# uC.net
KiCad netlist of a schematic drawn in Altium Designer
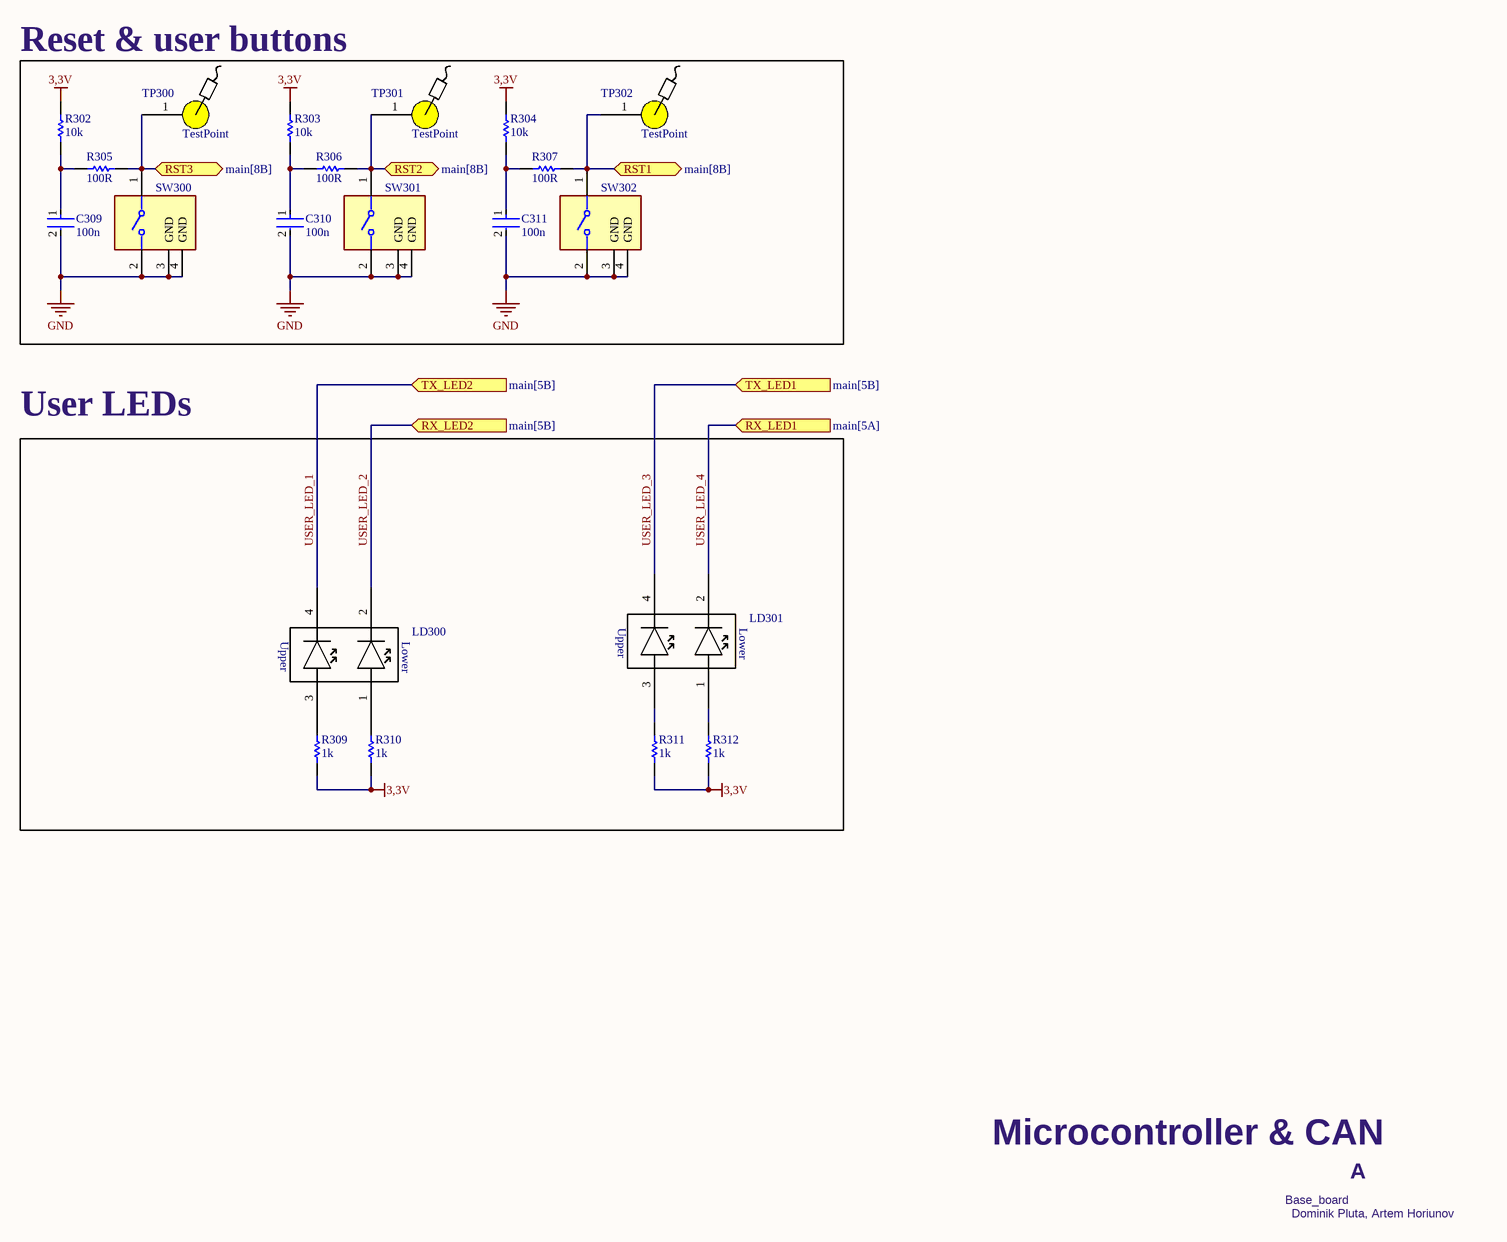
[diagram p0: uC.SchDoc]

(export (version "E")
  (design (tool "Eeschema 10.0.6"))
  (components
    (comp (ref "C309")
      (value "100n")
      (footprint "FP-C0603C-CF-MFG")
      (description "CAP CER 0.1UF 50V X7R 0603")
      (fields (field (name "TOLERANCE") "0.1") (field (name "MANUFACTURER") "KEMET"))
      (libsource (lib "Altium Content Vault") (part "b4654b650e69147ec39a6b967a45e02"))
    )
    (comp (ref "C310")
      (value "100n")
      (footprint "FP-C0603C-CF-MFG")
      (description "CAP CER 0.1UF 50V X7R 0603")
      (fields (field (name "TOLERANCE") "0.1") (field (name "MANUFACTURER") "KEMET"))
      (libsource (lib "Altium Content Vault") (part "b4654b650e69147ec39a6b967a45e02"))
    )
    (comp (ref "C311")
      (value "100n")
      (footprint "FP-C0603C-CF-MFG")
      (description "CAP CER 0.1UF 50V X7R 0603")
      (fields (field (name "TOLERANCE") "0.1") (field (name "MANUFACTURER") "KEMET"))
      (libsource (lib "Altium Content Vault") (part "b4654b650e69147ec39a6b967a45e02"))
    )
    (comp (ref "LD300")
      (value "~")
      (footprint "LedHolder:LED_HOLDER")
      (libsource (lib "LedHolder") (part "DoubleStack_Side_Led_3mm"))
    )
    (comp (ref "LD301")
      (value "~")
      (footprint "LedHolder:LED_HOLDER")
      (libsource (lib "LedHolder") (part "DoubleStack_Side_Led_3mm"))
    )
    (comp (ref "R302")
      (value "10k")
      (footprint "RESC0603(1608)_N")
      (description "0.1W 5% 0603 (1608 Metric)  SMD")
      (fields (field (name "TOLERANCE") "5 %") (field (name "POWER") "0.1 W"))
      (libsource (lib "Altium Content Vault") (part "RES"))
    )
    (comp (ref "R303")
      (value "10k")
      (footprint "RESC0603(1608)_N")
      (description "0.1W 5% 0603 (1608 Metric)  SMD")
      (fields (field (name "TOLERANCE") "5 %") (field (name "POWER") "0.1 W"))
      (libsource (lib "Altium Content Vault") (part "RES"))
    )
    (comp (ref "R304")
      (value "10k")
      (footprint "RESC0603(1608)_N")
      (description "0.1W 5% 0603 (1608 Metric)  SMD")
      (fields (field (name "TOLERANCE") "5 %") (field (name "POWER") "0.1 W"))
      (libsource (lib "Altium Content Vault") (part "RES"))
    )
    (comp (ref "R305")
      (value "100R")
      (footprint "RESC0603(1608)_N")
      (description "0.1W 5% 0603 (1608 Metric)  SMD")
      (fields (field (name "TOLERANCE") "5 %") (field (name "POWER") "0.1 W"))
      (libsource (lib "Altium Content Vault") (part "RES"))
    )
    (comp (ref "R306")
      (value "100R")
      (footprint "RESC0603(1608)_N")
      (description "0.1W 5% 0603 (1608 Metric)  SMD")
      (fields (field (name "TOLERANCE") "5 %") (field (name "POWER") "0.1 W"))
      (libsource (lib "Altium Content Vault") (part "RES"))
    )
    (comp (ref "R307")
      (value "100R")
      (footprint "RESC0603(1608)_N")
      (description "0.1W 5% 0603 (1608 Metric)  SMD")
      (fields (field (name "TOLERANCE") "5 %") (field (name "POWER") "0.1 W"))
      (libsource (lib "Altium Content Vault") (part "RES"))
    )
    (comp (ref "R309")
      (value "1k")
      (footprint "RESC0603(1608)_N")
      (description "0.1W 1% 0603 (1608 Metric)  SMD")
      (fields (field (name "TOLERANCE") "5 %") (field (name "POWER") "0.1 W"))
      (libsource (lib "Altium Content Vault") (part "RES"))
    )
    (comp (ref "R310")
      (value "1k")
      (footprint "RESC0603(1608)_N")
      (description "0.1W 1% 0603 (1608 Metric)  SMD")
      (fields (field (name "TOLERANCE") "5 %") (field (name "POWER") "0.1 W"))
      (libsource (lib "Altium Content Vault") (part "RES"))
    )
    (comp (ref "R311")
      (value "1k")
      (footprint "RESC0603(1608)_N")
      (description "0.1W 1% 0603 (1608 Metric)  SMD")
      (fields (field (name "TOLERANCE") "5 %") (field (name "POWER") "0.1 W"))
      (libsource (lib "Altium Content Vault") (part "RES"))
    )
    (comp (ref "R312")
      (value "1k")
      (footprint "RESC0603(1608)_N")
      (description "0.1W 1% 0603 (1608 Metric)  SMD")
      (fields (field (name "TOLERANCE") "5 %") (field (name "POWER") "0.1 W"))
      (libsource (lib "Altium Content Vault") (part "RES"))
    )
    (comp (ref "SW300")
      (value "B3F-3122")
      (footprint "FP-B3F-3122-MFG")
      (description "SWITCH TACTILE SPST-NO 0.05A 24V")
      (libsource (lib "Altium Content Vault") (part "05c531d4b500f7e9514fa3f65f375ae"))
    )
    (comp (ref "SW301")
      (value "B3F-3122")
      (footprint "FP-B3F-3122-MFG")
      (description "SWITCH TACTILE SPST-NO 0.05A 24V")
      (libsource (lib "Altium Content Vault") (part "05c531d4b500f7e9514fa3f65f375ae"))
    )
    (comp (ref "SW302")
      (value "B3F-3122")
      (footprint "FP-B3F-3122-MFG")
      (description "SWITCH TACTILE SPST-NO 0.05A 24V")
      (libsource (lib "Altium Content Vault") (part "05c531d4b500f7e9514fa3f65f375ae"))
    )
    (comp (ref "TP300")
      (value "TestPoint")
      (footprint "TestPoint")
      (libsource (lib "TestPoint") (part "TestPoint"))
    )
    (comp (ref "TP301")
      (value "TestPoint")
      (footprint "TestPoint")
      (libsource (lib "TestPoint") (part "TestPoint"))
    )
    (comp (ref "TP302")
      (value "TestPoint")
      (footprint "TestPoint")
      (libsource (lib "TestPoint") (part "TestPoint"))
    )
  )
  (nets
    (net (code "1") (name "/RST1") (class "Default")
      (node (ref "R307") (pin "1") (pinfunction "1_1") (pintype "passive"))
      (node (ref "SW302") (pin "1") (pinfunction "1_1") (pintype "passive"))
      (node (ref "TP302") (pin "1") (pintype "passive"))
    )
    (net (code "2") (name "/RST2") (class "Default")
      (node (ref "R306") (pin "1") (pinfunction "1_1") (pintype "passive"))
      (node (ref "SW301") (pin "1") (pinfunction "1_1") (pintype "passive"))
      (node (ref "TP301") (pin "1") (pintype "passive"))
    )
    (net (code "3") (name "/RST3") (class "Default")
      (node (ref "R305") (pin "1") (pinfunction "1_1") (pintype "passive"))
      (node (ref "SW300") (pin "1") (pinfunction "1_1") (pintype "passive"))
      (node (ref "TP300") (pin "1") (pintype "passive"))
    )
    (net (code "4") (name "/USER_LED_1") (class "Default") (node (ref "LD300") (pin "4") (pintype "passive")))
    (net (code "5") (name "/USER_LED_2") (class "Default") (node (ref "LD300") (pin "2") (pintype "passive")))
    (net (code "6") (name "/USER_LED_3") (class "Default") (node (ref "LD301") (pin "4") (pintype "passive")))
    (net (code "7") (name "/USER_LED_4") (class "Default") (node (ref "LD301") (pin "2") (pintype "passive")))
    (net (code "8") (name "3,3V") (class "Default")
      (node (ref "R302") (pin "2") (pinfunction "2_2") (pintype "passive"))
      (node (ref "R303") (pin "2") (pinfunction "2_2") (pintype "passive"))
      (node (ref "R304") (pin "2") (pinfunction "2_2") (pintype "passive"))
      (node (ref "R309") (pin "1") (pinfunction "1_1") (pintype "passive"))
      (node (ref "R310") (pin "1") (pinfunction "1_1") (pintype "passive"))
      (node (ref "R311") (pin "1") (pinfunction "1_1") (pintype "passive"))
      (node (ref "R312") (pin "1") (pinfunction "1_1") (pintype "passive"))
    )
    (net (code "9") (name "GND") (class "Default")
      (node (ref "C309") (pin "2") (pinfunction "2_2") (pintype "passive"))
      (node (ref "C310") (pin "2") (pinfunction "2_2") (pintype "passive"))
      (node (ref "C311") (pin "2") (pinfunction "2_2") (pintype "passive"))
      (node (ref "SW300") (pin "2") (pinfunction "2_2") (pintype "passive"))
      (node (ref "SW300") (pin "3") (pinfunction "GND_3") (pintype "power_in"))
      (node (ref "SW300") (pin "4") (pinfunction "GND_4") (pintype "power_in"))
      (node (ref "SW301") (pin "2") (pinfunction "2_2") (pintype "passive"))
      (node (ref "SW301") (pin "3") (pinfunction "GND_3") (pintype "power_in"))
      (node (ref "SW301") (pin "4") (pinfunction "GND_4") (pintype "power_in"))
      (node (ref "SW302") (pin "2") (pinfunction "2_2") (pintype "passive"))
      (node (ref "SW302") (pin "3") (pinfunction "GND_3") (pintype "power_in"))
      (node (ref "SW302") (pin "4") (pinfunction "GND_4") (pintype "power_in"))
    )
    (net (code "10") (name "Net-(C309-Pad1)") (class "Default")
      (node (ref "C309") (pin "1") (pinfunction "1_1") (pintype "passive"))
      (node (ref "R302") (pin "1") (pinfunction "1_1") (pintype "passive"))
      (node (ref "R305") (pin "2") (pinfunction "2_2") (pintype "passive"))
    )
    (net (code "11") (name "Net-(C310-Pad1)") (class "Default")
      (node (ref "C310") (pin "1") (pinfunction "1_1") (pintype "passive"))
      (node (ref "R303") (pin "1") (pinfunction "1_1") (pintype "passive"))
      (node (ref "R306") (pin "2") (pinfunction "2_2") (pintype "passive"))
    )
    (net (code "12") (name "Net-(C311-Pad1)") (class "Default")
      (node (ref "C311") (pin "1") (pinfunction "1_1") (pintype "passive"))
      (node (ref "R304") (pin "1") (pinfunction "1_1") (pintype "passive"))
      (node (ref "R307") (pin "2") (pinfunction "2_2") (pintype "passive"))
    )
    (net (code "13") (name "Net-(LD300-Pad1)") (class "Default")
      (node (ref "LD300") (pin "1") (pintype "passive"))
      (node (ref "R310") (pin "2") (pinfunction "2_2") (pintype "passive"))
    )
    (net (code "14") (name "Net-(LD300-Pad3)") (class "Default")
      (node (ref "LD300") (pin "3") (pintype "passive"))
      (node (ref "R309") (pin "2") (pinfunction "2_2") (pintype "passive"))
    )
    (net (code "15") (name "Net-(LD301-Pad1)") (class "Default")
      (node (ref "LD301") (pin "1") (pintype "passive"))
      (node (ref "R312") (pin "2") (pinfunction "2_2") (pintype "passive"))
    )
    (net (code "16") (name "Net-(LD301-Pad3)") (class "Default")
      (node (ref "LD301") (pin "3") (pintype "passive"))
      (node (ref "R311") (pin "2") (pinfunction "2_2") (pintype "passive"))
    )
  )
)
